# schematic.net
KiCad netlist of a schematic drawn in EAGLE
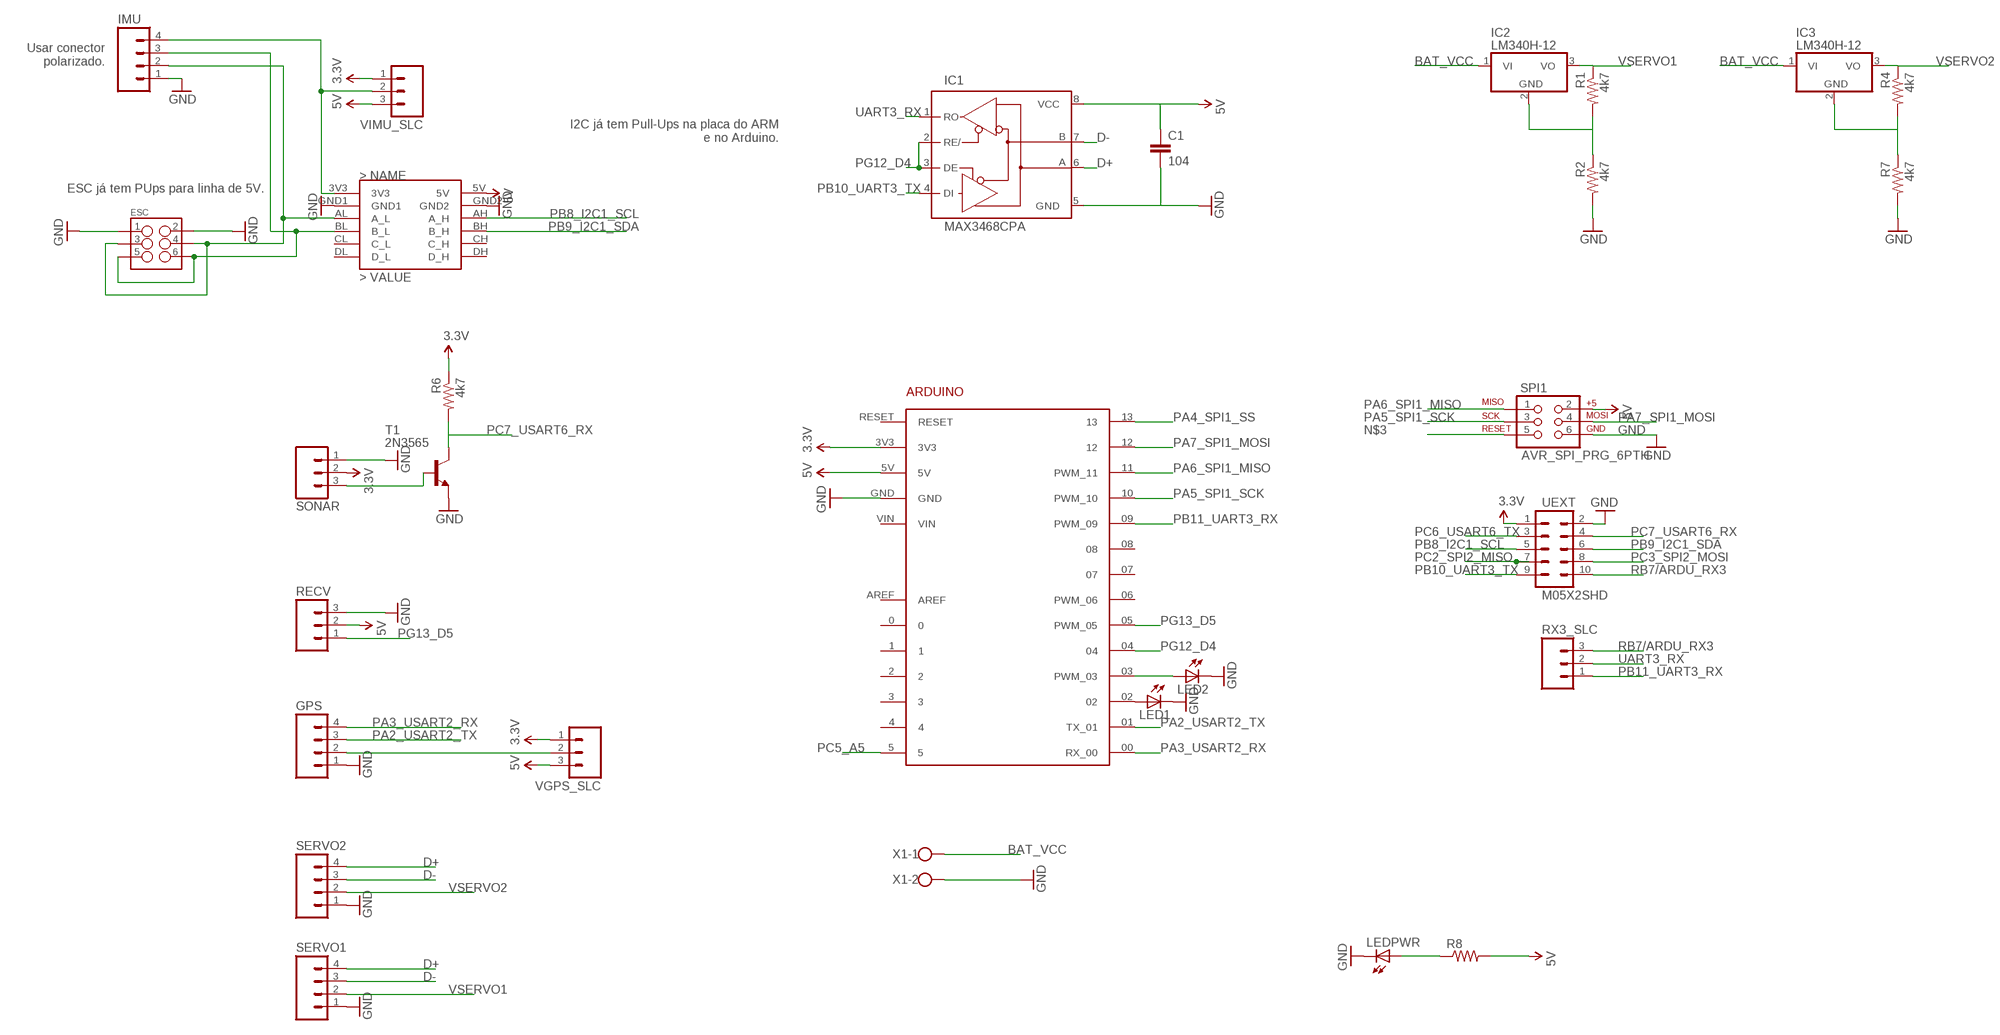
[diagram p0: schematic, sheet 1]

(export (version "E")
  (design (tool "Eeschema 10.0.6"))
  (components
    (comp (ref "ARDUINO1")
      (value "ARDUINO")
      (footprint "eagle-import:ARDUINO")
      (libsource (lib "eagle-import") (part "ARDUINO"))
    )
    (comp (ref "C1")
      (value "104")
      (footprint "eagle-import:CAP-PTH-SMALL-KIT")
      (libsource (lib "eagle-import") (part "0.1UF-50V-20%(PTH)KIT-EZ"))
    )
    (comp (ref "ESC")
      (value "M03X22X3_SILK_SM")
      (footprint "eagle-import:2X3")
      (libsource (lib "eagle-import") (part "M03X22X3_SILK_SM"))
    )
    (comp (ref "GPS")
      (value "M04PTH")
      (footprint "eagle-import:1X04")
      (libsource (lib "eagle-import") (part "M04PTH"))
    )
    (comp (ref "IC1")
      (value "MAX3468CPA")
      (footprint "eagle-import:DIL08")
      (libsource (lib "eagle-import") (part "MAX34PA68C"))
    )
    (comp (ref "IC2")
      (value "LM340H-12")
      (footprint "eagle-import:TO220H")
      (libsource (lib "eagle-import") (part "LM340?-H12"))
    )
    (comp (ref "IC3")
      (value "LM340H-12")
      (footprint "eagle-import:TO220H")
      (libsource (lib "eagle-import") (part "LM340?-H12"))
    )
    (comp (ref "IMU")
      (value "M04PTH")
      (footprint "eagle-import:1X04")
      (libsource (lib "eagle-import") (part "M04PTH"))
    )
    (comp (ref "LED1")
      (value "LED3MM")
      (footprint "eagle-import:LED3MM")
      (libsource (lib "eagle-import") (part "LED3MM"))
    )
    (comp (ref "LED2")
      (value "LED3MM")
      (footprint "eagle-import:LED3MM")
      (libsource (lib "eagle-import") (part "LED3MM"))
    )
    (comp (ref "LEDPWR")
      (value "LED3MM")
      (footprint "eagle-import:LED3MM")
      (libsource (lib "eagle-import") (part "LED3MM"))
    )
    (comp (ref "R1")
      (value "4k7")
      (footprint "eagle-import:0309V")
      (libsource (lib "eagle-import") (part "R-US_0309/V"))
    )
    (comp (ref "R2")
      (value "4k7")
      (footprint "eagle-import:0204_7")
      (libsource (lib "eagle-import") (part "R-US_0204/7"))
    )
    (comp (ref "R4")
      (value "4k7")
      (footprint "eagle-import:0309V")
      (libsource (lib "eagle-import") (part "R-US_0309/V"))
    )
    (comp (ref "R6")
      (value "4k7")
      (footprint "eagle-import:M1406")
      (libsource (lib "eagle-import") (part "R-US_M1406"))
    )
    (comp (ref "R7")
      (value "4k7")
      (footprint "eagle-import:0204_7")
      (libsource (lib "eagle-import") (part "R-US_0204/7"))
    )
    (comp (ref "R8")
      (value "RESISTORPTH-1/6W")
      (footprint "eagle-import:1_6W-RES")
      (libsource (lib "eagle-import") (part "RESISTORPTH-1/6W"))
    )
    (comp (ref "RECV")
      (value "M03PTH")
      (footprint "eagle-import:1X03")
      (libsource (lib "eagle-import") (part "M03PTH"))
    )
    (comp (ref "RX3_SLC")
      (value "M03PTH")
      (footprint "eagle-import:1X03")
      (libsource (lib "eagle-import") (part "M03PTH"))
    )
    (comp (ref "SERVO1")
      (value "M04PTH")
      (footprint "eagle-import:1X04")
      (libsource (lib "eagle-import") (part "M04PTH"))
    )
    (comp (ref "SERVO2")
      (value "M04PTH")
      (footprint "eagle-import:1X04")
      (libsource (lib "eagle-import") (part "M04PTH"))
    )
    (comp (ref "SONAR")
      (value "M03PTH")
      (footprint "eagle-import:1X03")
      (libsource (lib "eagle-import") (part "M03PTH"))
    )
    (comp (ref "SPI1")
      (value "AVR_SPI_PRG_6PTH")
      (footprint "eagle-import:2X3")
      (libsource (lib "eagle-import") (part "AVR_SPI_PRG_6PTH"))
    )
    (comp (ref "T1")
      (value "2N3565")
      (footprint "eagle-import:TO92")
      (libsource (lib "eagle-import") (part "2N3565"))
    )
    (comp (ref "U$1")
      (value "JYMCU_LOGIC_LEVEL_CONVERTER")
      (footprint "eagle-import:JYMCU_LOGIC_LEVEL_SHIFTER_DIP")
      (libsource (lib "eagle-import") (part "JYMCU_LOGIC_LEVEL_CONVERTER"))
    )
    (comp (ref "UEXT")
      (value "M05X2SHD")
      (footprint "eagle-import:2X5-SHROUDED")
      (libsource (lib "eagle-import") (part "M05X2SHD"))
    )
    (comp (ref "VGPS_SLC")
      (value "M03PTH")
      (footprint "eagle-import:1X03")
      (libsource (lib "eagle-import") (part "M03PTH"))
    )
    (comp (ref "VIMU_SLC")
      (value "M03PTH")
      (footprint "eagle-import:1X03")
      (libsource (lib "eagle-import") (part "M03PTH"))
    )
    (comp (ref "X1")
      (value "W237-102")
      (footprint "eagle-import:W237-102")
      (fields (field (name "MPN") "237-102"))
      (libsource (lib "eagle-import") (part "W237-102"))
    )
  )
  (nets
    (net (code "1") (name "/BAT_VCC") (class "Default")
      (node (ref "IC2") (pin "1") (pinfunction "VI_1") (pintype "input"))
      (node (ref "IC3") (pin "1") (pinfunction "VI_1") (pintype "input"))
      (node (ref "X1") (pin "1") (pinfunction "KL_1") (pintype "passive"))
    )
    (net (code "2") (name "/D+") (class "Default")
      (node (ref "IC1") (pin "6") (pinfunction "A_6") (pintype "passive"))
      (node (ref "SERVO1") (pin "4") (pinfunction "4_4") (pintype "passive"))
      (node (ref "SERVO2") (pin "4") (pinfunction "4_4") (pintype "passive"))
    )
    (net (code "3") (name "/D-") (class "Default")
      (node (ref "IC1") (pin "7") (pinfunction "B_7") (pintype "passive"))
      (node (ref "SERVO1") (pin "3") (pinfunction "3_3") (pintype "passive"))
      (node (ref "SERVO2") (pin "3") (pinfunction "3_3") (pintype "passive"))
    )
    (net (code "4") (name "/N$3") (class "Default")
      (node (ref "SPI1") (pin "5") (pinfunction "5_5") (pintype "passive"))
    )
    (net (code "5") (name "/PA2_USART2_TX") (class "Default")
      (node (ref "ARDUINO1") (pin "01") (pinfunction "TX_01_01") (pintype "bidirectional"))
      (node (ref "GPS") (pin "3") (pinfunction "3_3") (pintype "passive"))
    )
    (net (code "6") (name "/PA3_USART2_RX") (class "Default")
      (node (ref "ARDUINO1") (pin "00") (pinfunction "RX_00_00") (pintype "bidirectional"))
      (node (ref "GPS") (pin "4") (pinfunction "4_4") (pintype "passive"))
    )
    (net (code "7") (name "/PA4_SPI1_SS") (class "Default")
      (node (ref "ARDUINO1") (pin "13") (pinfunction "13_13") (pintype "bidirectional"))
    )
    (net (code "8") (name "/PA5_SPI1_SCK") (class "Default")
      (node (ref "ARDUINO1") (pin "10") (pinfunction "PWM_10_10") (pintype "bidirectional"))
      (node (ref "SPI1") (pin "3") (pinfunction "3_3") (pintype "passive"))
    )
    (net (code "9") (name "/PA6_SPI1_MISO") (class "Default")
      (node (ref "ARDUINO1") (pin "11") (pinfunction "PWM_11_11") (pintype "bidirectional"))
      (node (ref "SPI1") (pin "1") (pinfunction "1_1") (pintype "passive"))
    )
    (net (code "10") (name "/PA7_SPI1_MOSI") (class "Default")
      (node (ref "ARDUINO1") (pin "12") (pinfunction "12_12") (pintype "bidirectional"))
      (node (ref "SPI1") (pin "4") (pinfunction "4_4") (pintype "passive"))
    )
    (net (code "11") (name "/PB8_I2C1_SCL") (class "Default")
      (node (ref "U$1") (pin "AH") (pinfunction "A_H_AH") (pintype "bidirectional"))
      (node (ref "UEXT") (pin "5") (pinfunction "5_5") (pintype "passive"))
    )
    (net (code "12") (name "/PB9_I2C1_SDA") (class "Default")
      (node (ref "U$1") (pin "BH") (pinfunction "B_H_BH") (pintype "bidirectional"))
      (node (ref "UEXT") (pin "6") (pinfunction "6_6") (pintype "passive"))
    )
    (net (code "13") (name "/PB10_UART3_TX") (class "Default")
      (node (ref "IC1") (pin "4") (pinfunction "DI_4") (pintype "input"))
      (node (ref "UEXT") (pin "9") (pinfunction "9_9") (pintype "passive"))
    )
    (net (code "14") (name "/PB11_UART3_RX") (class "Default")
      (node (ref "ARDUINO1") (pin "09") (pinfunction "PWM_09_09") (pintype "bidirectional"))
      (node (ref "RX3_SLC") (pin "1") (pinfunction "1_1") (pintype "passive"))
    )
    (net (code "15") (name "/PC2_SPI2_MISO") (class "Default")
      (node (ref "UEXT") (pin "7") (pinfunction "7_7") (pintype "passive"))
    )
    (net (code "16") (name "/PC3_SPI2_MOSI") (class "Default")
      (node (ref "UEXT") (pin "8") (pinfunction "8_8") (pintype "passive"))
    )
    (net (code "17") (name "/PC5_A5") (class "Default")
      (node (ref "ARDUINO1") (pin "5") (pinfunction "5_5") (pintype "bidirectional"))
    )
    (net (code "18") (name "/PC6_USART6_TX") (class "Default")
      (node (ref "UEXT") (pin "3") (pinfunction "3_3") (pintype "passive"))
    )
    (net (code "19") (name "/PC7_USART6_RX") (class "Default")
      (node (ref "R6") (pin "2") (pinfunction "2_2") (pintype "passive"))
      (node (ref "T1") (pin "1") (pinfunction "C_1") (pintype "passive"))
      (node (ref "UEXT") (pin "4") (pinfunction "4_4") (pintype "passive"))
    )
    (net (code "20") (name "/PG12_D4") (class "Default")
      (node (ref "ARDUINO1") (pin "04") (pinfunction "04_04") (pintype "bidirectional"))
      (node (ref "IC1") (pin "2") (pinfunction "RE/_2") (pintype "input"))
      (node (ref "IC1") (pin "3") (pinfunction "DE_3") (pintype "input"))
    )
    (net (code "21") (name "/PG13_D5") (class "Default")
      (node (ref "ARDUINO1") (pin "05") (pinfunction "PWM_05_05") (pintype "bidirectional"))
      (node (ref "RECV") (pin "1") (pinfunction "1_1") (pintype "passive"))
    )
    (net (code "22") (name "/RB7{slash}ARDU_RX3") (class "Default")
      (node (ref "RX3_SLC") (pin "3") (pinfunction "3_3") (pintype "passive"))
      (node (ref "UEXT") (pin "10") (pinfunction "10_10") (pintype "passive"))
    )
    (net (code "23") (name "/UART3_RX") (class "Default")
      (node (ref "IC1") (pin "1") (pinfunction "RO_1") (pintype "output"))
      (node (ref "RX3_SLC") (pin "2") (pinfunction "2_2") (pintype "passive"))
    )
    (net (code "24") (name "/VSERVO1") (class "Default")
      (node (ref "IC2") (pin "3") (pinfunction "VO_3") (pintype "passive"))
      (node (ref "R1") (pin "1") (pinfunction "1_1") (pintype "passive"))
      (node (ref "SERVO1") (pin "2") (pinfunction "2_2") (pintype "passive"))
    )
    (net (code "25") (name "/VSERVO2") (class "Default")
      (node (ref "IC3") (pin "3") (pinfunction "VO_3") (pintype "passive"))
      (node (ref "R4") (pin "1") (pinfunction "1_1") (pintype "passive"))
      (node (ref "SERVO2") (pin "2") (pinfunction "2_2") (pintype "passive"))
    )
    (net (code "26") (name "3.3V") (class "Default")
      (node (ref "ARDUINO1") (pin "3V3") (pinfunction "3V3_3V3") (pintype "bidirectional"))
      (node (ref "R6") (pin "1") (pinfunction "1_1") (pintype "passive"))
      (node (ref "SONAR") (pin "2") (pinfunction "2_2") (pintype "passive"))
      (node (ref "UEXT") (pin "1") (pinfunction "1_1") (pintype "passive"))
      (node (ref "VGPS_SLC") (pin "1") (pinfunction "1_1") (pintype "passive"))
      (node (ref "VIMU_SLC") (pin "1") (pinfunction "1_1") (pintype "passive"))
    )
    (net (code "27") (name "5V") (class "Default")
      (node (ref "ARDUINO1") (pin "5V") (pinfunction "5V_5V") (pintype "bidirectional"))
      (node (ref "C1") (pin "1") (pinfunction "1_1") (pintype "passive"))
      (node (ref "IC1") (pin "8") (pinfunction "VCC_8") (pintype "power_in"))
      (node (ref "R8") (pin "2") (pinfunction "2_2") (pintype "passive"))
      (node (ref "RECV") (pin "2") (pinfunction "2_2") (pintype "passive"))
      (node (ref "SPI1") (pin "2") (pinfunction "2_2") (pintype "passive"))
      (node (ref "U$1") (pin "5V") (pinfunction "5V_5V") (pintype "bidirectional"))
      (node (ref "VGPS_SLC") (pin "3") (pinfunction "3_3") (pintype "passive"))
      (node (ref "VIMU_SLC") (pin "3") (pinfunction "3_3") (pintype "passive"))
    )
    (net (code "28") (name "GND") (class "Default")
      (node (ref "ARDUINO1") (pin "GND") (pinfunction "GND_GND") (pintype "bidirectional"))
      (node (ref "C1") (pin "2") (pinfunction "2_2") (pintype "passive"))
      (node (ref "ESC") (pin "1") (pinfunction "1_1") (pintype "bidirectional"))
      (node (ref "ESC") (pin "2") (pinfunction "2_2") (pintype "bidirectional"))
      (node (ref "GPS") (pin "1") (pinfunction "1_1") (pintype "passive"))
      (node (ref "IC1") (pin "5") (pinfunction "GND_5") (pintype "power_in"))
      (node (ref "IMU") (pin "1") (pinfunction "1_1") (pintype "passive"))
      (node (ref "LED1") (pin "K") (pinfunction "C_K") (pintype "passive"))
      (node (ref "LED2") (pin "K") (pinfunction "C_K") (pintype "passive"))
      (node (ref "LEDPWR") (pin "K") (pinfunction "C_K") (pintype "passive"))
      (node (ref "R2") (pin "2") (pinfunction "2_2") (pintype "passive"))
      (node (ref "R7") (pin "2") (pinfunction "2_2") (pintype "passive"))
      (node (ref "RECV") (pin "3") (pinfunction "3_3") (pintype "passive"))
      (node (ref "SERVO1") (pin "1") (pinfunction "1_1") (pintype "passive"))
      (node (ref "SERVO2") (pin "1") (pinfunction "1_1") (pintype "passive"))
      (node (ref "SONAR") (pin "1") (pinfunction "1_1") (pintype "passive"))
      (node (ref "SPI1") (pin "6") (pinfunction "6_6") (pintype "passive"))
      (node (ref "T1") (pin "3") (pinfunction "E_3") (pintype "passive"))
      (node (ref "U$1") (pin "GND1") (pinfunction "GND1_GND1") (pintype "bidirectional"))
      (node (ref "U$1") (pin "GND2") (pinfunction "GND2_GND2") (pintype "bidirectional"))
      (node (ref "UEXT") (pin "2") (pinfunction "2_2") (pintype "passive"))
      (node (ref "X1") (pin "2") (pinfunction "KL_2") (pintype "passive"))
    )
    (net (code "29") (name "Net-(ARDUINO1-PWM_03)") (class "Default")
      (node (ref "ARDUINO1") (pin "03") (pinfunction "PWM_03_03") (pintype "bidirectional"))
      (node (ref "LED2") (pin "A") (pinfunction "A_A") (pintype "passive"))
    )
    (net (code "30") (name "Net-(ARDUINO1-Pad02)") (class "Default")
      (node (ref "ARDUINO1") (pin "02") (pinfunction "02_02") (pintype "bidirectional"))
      (node (ref "LED1") (pin "A") (pinfunction "A_A") (pintype "passive"))
    )
    (net (code "31") (name "Net-(GPS-Pad2)") (class "Default")
      (node (ref "GPS") (pin "2") (pinfunction "2_2") (pintype "passive"))
      (node (ref "VGPS_SLC") (pin "2") (pinfunction "2_2") (pintype "passive"))
    )
    (net (code "32") (name "Net-(IC2-GND)") (class "Default")
      (node (ref "IC2") (pin "2") (pinfunction "GND_2") (pintype "passive"))
      (node (ref "R1") (pin "2") (pinfunction "2_2") (pintype "passive"))
      (node (ref "R2") (pin "1") (pinfunction "1_1") (pintype "passive"))
    )
    (net (code "33") (name "Net-(IC3-GND)") (class "Default")
      (node (ref "IC3") (pin "2") (pinfunction "GND_2") (pintype "passive"))
      (node (ref "R4") (pin "2") (pinfunction "2_2") (pintype "passive"))
      (node (ref "R7") (pin "1") (pinfunction "1_1") (pintype "passive"))
    )
    (net (code "34") (name "Net-(IMU-Pad4)") (class "Default")
      (node (ref "IMU") (pin "4") (pinfunction "4_4") (pintype "passive"))
      (node (ref "U$1") (pin "3V3") (pinfunction "3V3_3V3") (pintype "bidirectional"))
      (node (ref "VIMU_SLC") (pin "2") (pinfunction "2_2") (pintype "passive"))
    )
    (net (code "35") (name "Net-(LEDPWR-PadA)") (class "Default")
      (node (ref "LEDPWR") (pin "A") (pinfunction "A_A") (pintype "passive"))
      (node (ref "R8") (pin "1") (pinfunction "1_1") (pintype "passive"))
    )
    (net (code "36") (name "Net-(T1-B)") (class "Default")
      (node (ref "SONAR") (pin "3") (pinfunction "3_3") (pintype "passive"))
      (node (ref "T1") (pin "2") (pinfunction "B_2") (pintype "passive"))
    )
    (net (code "37") (name "Net-(U$1-A_L)") (class "Default")
      (node (ref "ESC") (pin "3") (pinfunction "3_3") (pintype "bidirectional"))
      (node (ref "ESC") (pin "4") (pinfunction "4_4") (pintype "bidirectional"))
      (node (ref "IMU") (pin "2") (pinfunction "2_2") (pintype "passive"))
      (node (ref "U$1") (pin "AL") (pinfunction "A_L_AL") (pintype "bidirectional"))
    )
    (net (code "38") (name "Net-(U$1-B_L)") (class "Default")
      (node (ref "ESC") (pin "5") (pinfunction "5_5") (pintype "bidirectional"))
      (node (ref "ESC") (pin "6") (pinfunction "6_6") (pintype "bidirectional"))
      (node (ref "IMU") (pin "3") (pinfunction "3_3") (pintype "passive"))
      (node (ref "U$1") (pin "BL") (pinfunction "B_L_BL") (pintype "bidirectional"))
    )
    (net (code "39") (name "unconnected-(ARDUINO1-PWM_06-Pad06)") (class "Default")
      (node (ref "ARDUINO1") (pin "06") (pinfunction "PWM_06_06") (pintype "bidirectional"))
    )
    (net (code "40") (name "unconnected-(ARDUINO1-Pad0)") (class "Default")
      (node (ref "ARDUINO1") (pin "0") (pinfunction "0_0") (pintype "bidirectional"))
    )
    (net (code "41") (name "unconnected-(ARDUINO1-Pad1)") (class "Default")
      (node (ref "ARDUINO1") (pin "1") (pinfunction "1_1") (pintype "bidirectional"))
    )
    (net (code "42") (name "unconnected-(ARDUINO1-Pad2)") (class "Default")
      (node (ref "ARDUINO1") (pin "2") (pinfunction "2_2") (pintype "bidirectional"))
    )
    (net (code "43") (name "unconnected-(ARDUINO1-Pad3)") (class "Default")
      (node (ref "ARDUINO1") (pin "3") (pinfunction "3_3") (pintype "bidirectional"))
    )
    (net (code "44") (name "unconnected-(ARDUINO1-Pad4)") (class "Default")
      (node (ref "ARDUINO1") (pin "4") (pinfunction "4_4") (pintype "bidirectional"))
    )
    (net (code "45") (name "unconnected-(ARDUINO1-Pad07)") (class "Default")
      (node (ref "ARDUINO1") (pin "07") (pinfunction "07_07") (pintype "bidirectional"))
    )
    (net (code "46") (name "unconnected-(ARDUINO1-Pad08)") (class "Default")
      (node (ref "ARDUINO1") (pin "08") (pinfunction "08_08") (pintype "bidirectional"))
    )
    (net (code "47") (name "unconnected-(ARDUINO1-PadAREF)") (class "Default")
      (node (ref "ARDUINO1") (pin "AREF") (pinfunction "AREF_AREF") (pintype "bidirectional"))
    )
    (net (code "48") (name "unconnected-(ARDUINO1-PadRESET)") (class "Default")
      (node (ref "ARDUINO1") (pin "RESET") (pinfunction "RESET_RESET") (pintype "bidirectional"))
    )
    (net (code "49") (name "unconnected-(ARDUINO1-PadVIN)") (class "Default")
      (node (ref "ARDUINO1") (pin "VIN") (pinfunction "VIN_VIN") (pintype "bidirectional"))
    )
    (net (code "50") (name "unconnected-(U$1-C_H-PadCH)") (class "Default")
      (node (ref "U$1") (pin "CH") (pinfunction "C_H_CH") (pintype "bidirectional"))
    )
    (net (code "51") (name "unconnected-(U$1-C_L-PadCL)") (class "Default")
      (node (ref "U$1") (pin "CL") (pinfunction "C_L_CL") (pintype "bidirectional"))
    )
    (net (code "52") (name "unconnected-(U$1-D_H-PadDH)") (class "Default")
      (node (ref "U$1") (pin "DH") (pinfunction "D_H_DH") (pintype "bidirectional"))
    )
    (net (code "53") (name "unconnected-(U$1-D_L-PadDL)") (class "Default")
      (node (ref "U$1") (pin "DL") (pinfunction "D_L_DL") (pintype "bidirectional"))
    )
  )
)
